# Elekid.net
KiCad netlist of a schematic drawn in Altium Designer
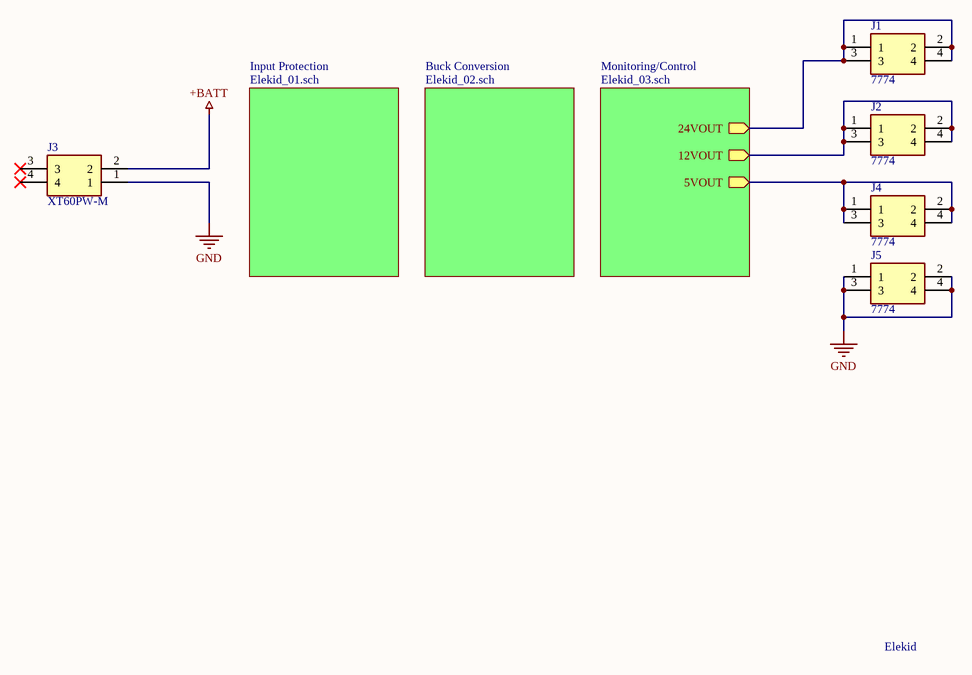
[diagram p0: Elekid.SchDoc]

(export (version "E")
  (design (tool "Eeschema 10.0.6"))
  (components
    (comp (ref "J1")
      (value "7774")
      (footprint "Embedded:7774")
      (description "Connector")
      (fields (field (name "MOUSER PART NUMBER") "534-7774"))
      (libsource (lib "Embedded") (part "7774"))
    )
    (comp (ref "J2")
      (value "7774")
      (footprint "Embedded:7774")
      (description "Connector")
      (fields (field (name "MOUSER PART NUMBER") "534-7774"))
      (libsource (lib "Embedded") (part "7774"))
    )
    (comp (ref "J3")
      (value "XT60PW-M")
      (footprint "Embedded:XT60PWM")
      (description "Connector")
      (libsource (lib "*") (part "XT60PW-M"))
    )
    (comp (ref "J4")
      (value "7774")
      (footprint "Embedded:7774")
      (description "Connector")
      (fields (field (name "MOUSER PART NUMBER") "534-7774"))
      (libsource (lib "Embedded") (part "7774"))
    )
    (comp (ref "J5")
      (value "7774")
      (footprint "Embedded:7774")
      (description "Connector")
      (fields (field (name "MOUSER PART NUMBER") "534-7774"))
      (libsource (lib "Embedded") (part "7774"))
    )
  )
  (nets
    (net (code "1") (name "+BATT") (class "Default")
      (node (ref "J3") (pin "2") (pinfunction "2_2") (pintype "passive"))
    )
    (net (code "2") (name "/5VOUT") (class "Default")
      (node (ref "J4") (pin "1") (pinfunction "1_1") (pintype "passive"))
      (node (ref "J4") (pin "2") (pinfunction "2_2") (pintype "passive"))
      (node (ref "J4") (pin "3") (pinfunction "3_3") (pintype "passive"))
      (node (ref "J4") (pin "4") (pinfunction "4_4") (pintype "passive"))
    )
    (net (code "3") (name "/12VOUT") (class "Default")
      (node (ref "J2") (pin "1") (pinfunction "1_1") (pintype "passive"))
      (node (ref "J2") (pin "2") (pinfunction "2_2") (pintype "passive"))
      (node (ref "J2") (pin "3") (pinfunction "3_3") (pintype "passive"))
      (node (ref "J2") (pin "4") (pinfunction "4_4") (pintype "passive"))
    )
    (net (code "4") (name "/24VOUT") (class "Default")
      (node (ref "J1") (pin "1") (pinfunction "1_1") (pintype "passive"))
      (node (ref "J1") (pin "2") (pinfunction "2_2") (pintype "passive"))
      (node (ref "J1") (pin "3") (pinfunction "3_3") (pintype "passive"))
      (node (ref "J1") (pin "4") (pinfunction "4_4") (pintype "passive"))
    )
    (net (code "5") (name "GND") (class "Default")
      (node (ref "J3") (pin "1") (pinfunction "1_1") (pintype "passive"))
      (node (ref "J5") (pin "1") (pinfunction "1_1") (pintype "passive"))
      (node (ref "J5") (pin "2") (pinfunction "2_2") (pintype "passive"))
      (node (ref "J5") (pin "3") (pinfunction "3_3") (pintype "passive"))
      (node (ref "J5") (pin "4") (pinfunction "4_4") (pintype "passive"))
    )
    (net (code "6") (name "unconnected-(J3-Pad3)") (class "Default")
      (node (ref "J3") (pin "3") (pinfunction "3_3") (pintype "passive+no_connect"))
    )
    (net (code "7") (name "unconnected-(J3-Pad4)") (class "Default")
      (node (ref "J3") (pin "4") (pinfunction "4_4") (pintype "passive+no_connect"))
    )
  )
)
